# Aux_Board_V5_2.net
KiCad netlist of a schematic drawn in EAGLE
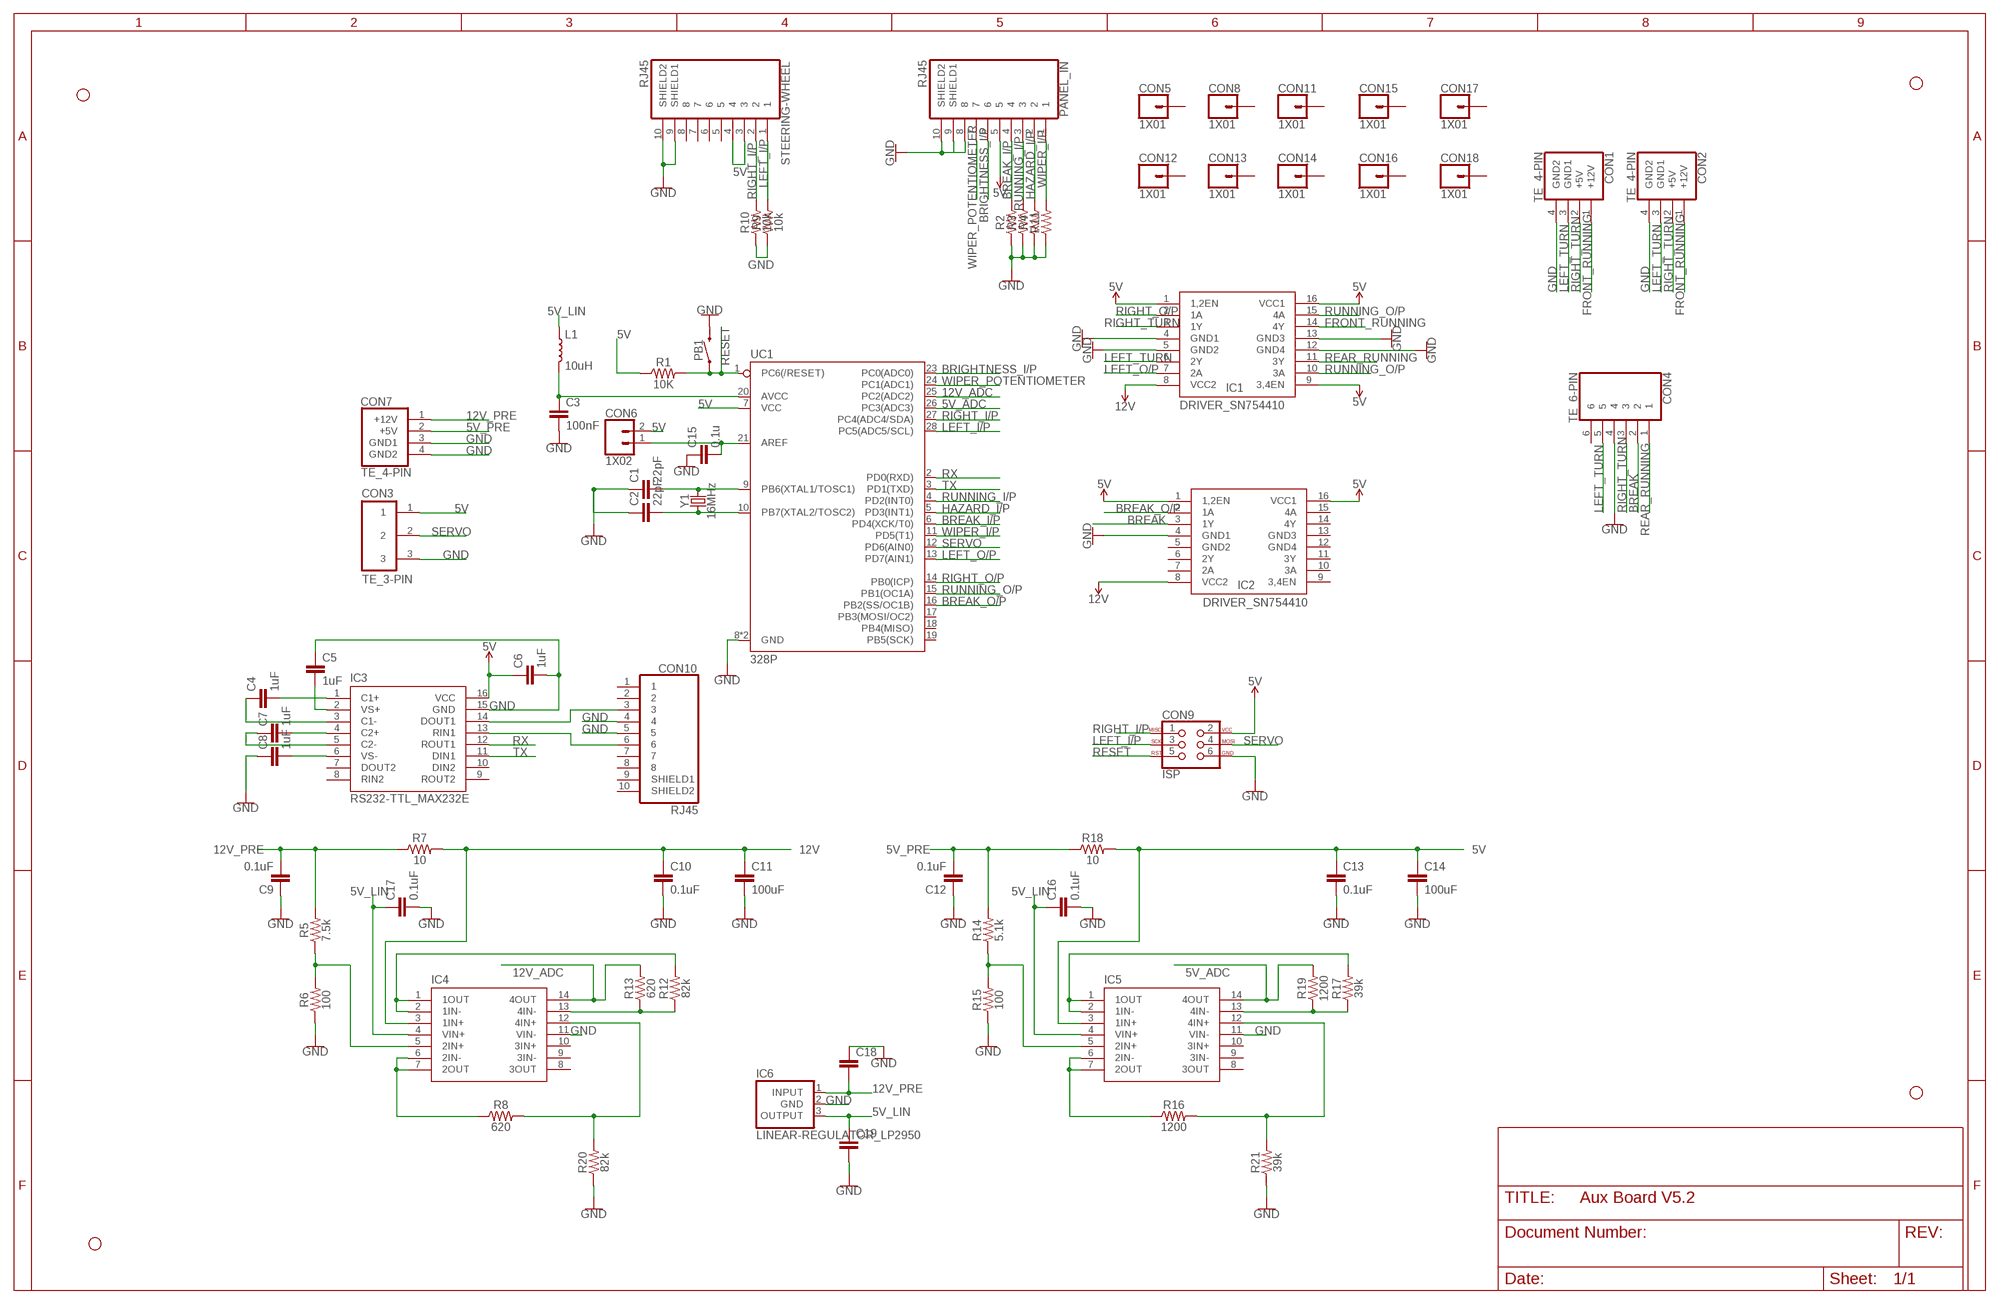
[diagram p0: schematic, sheet 1]

(export (version "E")
  (design (tool "Eeschema 10.0.6"))
  (components
    (comp (ref "C1")
      (value "22pF")
      (footprint "eagle-import:0805")
      (libsource (lib "eagle-import") (part "CAPACITOR_0805"))
    )
    (comp (ref "C2")
      (value "22pF")
      (footprint "eagle-import:0805")
      (libsource (lib "eagle-import") (part "CAPACITOR_0805"))
    )
    (comp (ref "C3")
      (value "100nF")
      (footprint "eagle-import:0805")
      (libsource (lib "eagle-import") (part "CAPACITOR_0805"))
    )
    (comp (ref "C4")
      (value "1uF")
      (footprint "eagle-import:0805")
      (libsource (lib "eagle-import") (part "CAPACITOR_0805"))
    )
    (comp (ref "C5")
      (value "1uF")
      (footprint "eagle-import:0805")
      (libsource (lib "eagle-import") (part "CAPACITOR_0805"))
    )
    (comp (ref "C6")
      (value "1uF")
      (footprint "eagle-import:0805")
      (libsource (lib "eagle-import") (part "CAPACITOR_0805"))
    )
    (comp (ref "C7")
      (value "1uF")
      (footprint "eagle-import:0805")
      (libsource (lib "eagle-import") (part "CAPACITOR_0805"))
    )
    (comp (ref "C8")
      (value "1uF")
      (footprint "eagle-import:0805")
      (libsource (lib "eagle-import") (part "CAPACITOR_0805"))
    )
    (comp (ref "C9")
      (value "0.1uF")
      (footprint "eagle-import:0805")
      (libsource (lib "eagle-import") (part "CAPACITOR_0805"))
    )
    (comp (ref "C10")
      (value "0.1uF")
      (footprint "eagle-import:0805")
      (libsource (lib "eagle-import") (part "CAPACITOR_0805"))
    )
    (comp (ref "C11")
      (value "100uF")
      (footprint "eagle-import:0805")
      (libsource (lib "eagle-import") (part "CAPACITOR_0805"))
    )
    (comp (ref "C12")
      (value "0.1uF")
      (footprint "eagle-import:0805")
      (libsource (lib "eagle-import") (part "CAPACITOR_0805"))
    )
    (comp (ref "C13")
      (value "0.1uF")
      (footprint "eagle-import:0805")
      (libsource (lib "eagle-import") (part "CAPACITOR_0805"))
    )
    (comp (ref "C14")
      (value "100uF")
      (footprint "eagle-import:0805")
      (libsource (lib "eagle-import") (part "CAPACITOR_0805"))
    )
    (comp (ref "C15")
      (value "0.1u")
      (footprint "eagle-import:0805")
      (libsource (lib "eagle-import") (part "CAPACITOR_0805"))
    )
    (comp (ref "C16")
      (value "0.1uF")
      (footprint "eagle-import:0805")
      (libsource (lib "eagle-import") (part "CAPACITOR_0805"))
    )
    (comp (ref "C17")
      (value "0.1uF")
      (footprint "eagle-import:0805")
      (libsource (lib "eagle-import") (part "CAPACITOR_0805"))
    )
    (comp (ref "C18")
      (value "CAPACITOR_0805")
      (footprint "eagle-import:0805")
      (libsource (lib "eagle-import") (part "CAPACITOR_0805"))
    )
    (comp (ref "C19")
      (value "CAPACITOR_0805")
      (footprint "eagle-import:0805")
      (libsource (lib "eagle-import") (part "CAPACITOR_0805"))
    )
    (comp (ref "CON1")
      (value "TE_4-PIN")
      (footprint "eagle-import:TE_4-PIN")
      (libsource (lib "eagle-import") (part "TE_4-PIN"))
    )
    (comp (ref "CON2")
      (value "TE_4-PIN")
      (footprint "eagle-import:TE_4-PIN")
      (libsource (lib "eagle-import") (part "TE_4-PIN"))
    )
    (comp (ref "CON3")
      (value "TE_3-PIN")
      (footprint "eagle-import:TE_3-PIN")
      (libsource (lib "eagle-import") (part "TE_3-PIN"))
    )
    (comp (ref "CON4")
      (value "TE_6-PIN")
      (footprint "eagle-import:TE_6-PIN")
      (libsource (lib "eagle-import") (part "TE_6-PIN"))
    )
    (comp (ref "CON5")
      (value "1X01")
      (footprint "eagle-import:1X01")
      (libsource (lib "eagle-import") (part "1X01"))
    )
    (comp (ref "CON6")
      (value "1X02")
      (footprint "eagle-import:1X02")
      (libsource (lib "eagle-import") (part "1X02"))
    )
    (comp (ref "CON7")
      (value "TE_4-PIN")
      (footprint "eagle-import:TE_4-PIN")
      (libsource (lib "eagle-import") (part "TE_4-PIN"))
    )
    (comp (ref "CON8")
      (value "1X01")
      (footprint "eagle-import:1X01")
      (libsource (lib "eagle-import") (part "1X01"))
    )
    (comp (ref "CON9")
      (value "ISP")
      (footprint "eagle-import:ISP_CONNECTOR")
      (libsource (lib "eagle-import") (part "ISP"))
    )
    (comp (ref "CON10")
      (value "RJ45")
      (footprint "eagle-import:RJ45")
      (libsource (lib "eagle-import") (part "RJ45"))
    )
    (comp (ref "CON11")
      (value "1X01")
      (footprint "eagle-import:1X01")
      (libsource (lib "eagle-import") (part "1X01"))
    )
    (comp (ref "CON12")
      (value "1X01")
      (footprint "eagle-import:1X01")
      (libsource (lib "eagle-import") (part "1X01"))
    )
    (comp (ref "CON13")
      (value "1X01")
      (footprint "eagle-import:1X01")
      (libsource (lib "eagle-import") (part "1X01"))
    )
    (comp (ref "CON14")
      (value "1X01")
      (footprint "eagle-import:1X01")
      (libsource (lib "eagle-import") (part "1X01"))
    )
    (comp (ref "CON15")
      (value "1X01")
      (footprint "eagle-import:1X01")
      (libsource (lib "eagle-import") (part "1X01"))
    )
    (comp (ref "CON16")
      (value "1X01")
      (footprint "eagle-import:1X01")
      (libsource (lib "eagle-import") (part "1X01"))
    )
    (comp (ref "CON17")
      (value "1X01")
      (footprint "eagle-import:1X01")
      (libsource (lib "eagle-import") (part "1X01"))
    )
    (comp (ref "CON18")
      (value "1X01")
      (footprint "eagle-import:1X01")
      (libsource (lib "eagle-import") (part "1X01"))
    )
    (comp (ref "H1")
      (value "STAND-OFF")
      (footprint "eagle-import:STAND-OFF")
      (libsource (lib "eagle-import") (part "STAND-OFF"))
    )
    (comp (ref "H2")
      (value "STAND-OFF")
      (footprint "eagle-import:STAND-OFF")
      (libsource (lib "eagle-import") (part "STAND-OFF"))
    )
    (comp (ref "H3")
      (value "STAND-OFF")
      (footprint "eagle-import:STAND-OFF")
      (libsource (lib "eagle-import") (part "STAND-OFF"))
    )
    (comp (ref "H4")
      (value "STAND-OFF")
      (footprint "eagle-import:STAND-OFF")
      (libsource (lib "eagle-import") (part "STAND-OFF"))
    )
    (comp (ref "IC1")
      (value "DRIVER_SN754410")
      (footprint "eagle-import:DIP16")
      (libsource (lib "eagle-import") (part "DRIVER_SN754410"))
    )
    (comp (ref "IC2")
      (value "DRIVER_SN754410")
      (footprint "eagle-import:DIP16")
      (libsource (lib "eagle-import") (part "DRIVER_SN754410"))
    )
    (comp (ref "IC3")
      (value "RS232-TTL_MAX232E")
      (footprint "eagle-import:DIP16")
      (libsource (lib "eagle-import") (part "RS232-TTL_MAX232E"))
    )
    (comp (ref "IC4")
      (value "OP-AMP_QUAD")
      (footprint "eagle-import:DIP14")
      (libsource (lib "eagle-import") (part "OP-AMP_QUAD"))
    )
    (comp (ref "IC5")
      (value "OP-AMP_QUAD")
      (footprint "eagle-import:DIP14")
      (libsource (lib "eagle-import") (part "OP-AMP_QUAD"))
    )
    (comp (ref "IC6")
      (value "LINEAR-REGULATOR_LP2950")
      (footprint "eagle-import:TO92")
      (libsource (lib "eagle-import") (part "LINEAR-REGULATOR_LP2950"))
    )
    (comp (ref "L1")
      (value "10uH")
      (footprint "eagle-import:0805")
      (libsource (lib "eagle-import") (part "INDUCTOR_0805"))
    )
    (comp (ref "PANEL_IN")
      (value "RJ45")
      (footprint "eagle-import:RJ45")
      (libsource (lib "eagle-import") (part "RJ45"))
    )
    (comp (ref "PB1")
      (value "PUSHBUTTON")
      (footprint "eagle-import:PUSHBUTTON")
      (libsource (lib "eagle-import") (part "PUSHBUTTON"))
    )
    (comp (ref "R1")
      (value "10K")
      (footprint "eagle-import:0805")
      (libsource (lib "eagle-import") (part "RESISTOR_0805"))
    )
    (comp (ref "R2")
      (value "RESISTOR_0805")
      (footprint "eagle-import:0805")
      (libsource (lib "eagle-import") (part "RESISTOR_0805"))
    )
    (comp (ref "R3")
      (value "RESISTOR_0805")
      (footprint "eagle-import:0805")
      (libsource (lib "eagle-import") (part "RESISTOR_0805"))
    )
    (comp (ref "R4")
      (value "RESISTOR_0805")
      (footprint "eagle-import:0805")
      (libsource (lib "eagle-import") (part "RESISTOR_0805"))
    )
    (comp (ref "R5")
      (value "7.5k")
      (footprint "eagle-import:0805")
      (libsource (lib "eagle-import") (part "RESISTOR_0805"))
    )
    (comp (ref "R6")
      (value "100")
      (footprint "eagle-import:0805")
      (libsource (lib "eagle-import") (part "RESISTOR_0805"))
    )
    (comp (ref "R7")
      (value "10")
      (footprint "eagle-import:1210")
      (libsource (lib "eagle-import") (part "RESISTOR_1210"))
    )
    (comp (ref "R8")
      (value "620")
      (footprint "eagle-import:0805")
      (libsource (lib "eagle-import") (part "RESISTOR_0805"))
    )
    (comp (ref "R9")
      (value "10k")
      (footprint "eagle-import:0805")
      (libsource (lib "eagle-import") (part "RESISTOR_0805"))
    )
    (comp (ref "R10")
      (value "10k")
      (footprint "eagle-import:0805")
      (libsource (lib "eagle-import") (part "RESISTOR_0805"))
    )
    (comp (ref "R11")
      (value "RESISTOR_0805")
      (footprint "eagle-import:0805")
      (libsource (lib "eagle-import") (part "RESISTOR_0805"))
    )
    (comp (ref "R12")
      (value "82k")
      (footprint "eagle-import:0805")
      (libsource (lib "eagle-import") (part "RESISTOR_0805"))
    )
    (comp (ref "R13")
      (value "620")
      (footprint "eagle-import:0805")
      (libsource (lib "eagle-import") (part "RESISTOR_0805"))
    )
    (comp (ref "R14")
      (value "5.1k")
      (footprint "eagle-import:0805")
      (libsource (lib "eagle-import") (part "RESISTOR_0805"))
    )
    (comp (ref "R15")
      (value "100")
      (footprint "eagle-import:0805")
      (libsource (lib "eagle-import") (part "RESISTOR_0805"))
    )
    (comp (ref "R16")
      (value "1200")
      (footprint "eagle-import:0805")
      (libsource (lib "eagle-import") (part "RESISTOR_0805"))
    )
    (comp (ref "R17")
      (value "39k")
      (footprint "eagle-import:0805")
      (libsource (lib "eagle-import") (part "RESISTOR_0805"))
    )
    (comp (ref "R18")
      (value "10")
      (footprint "eagle-import:1210")
      (libsource (lib "eagle-import") (part "RESISTOR_1210"))
    )
    (comp (ref "R19")
      (value "1200")
      (footprint "eagle-import:0805")
      (libsource (lib "eagle-import") (part "RESISTOR_0805"))
    )
    (comp (ref "R20")
      (value "82k")
      (footprint "eagle-import:0805")
      (libsource (lib "eagle-import") (part "RESISTOR_0805"))
    )
    (comp (ref "R21")
      (value "39k")
      (footprint "eagle-import:0805")
      (libsource (lib "eagle-import") (part "RESISTOR_0805"))
    )
    (comp (ref "STEERING-WHEEL")
      (value "RJ45")
      (footprint "eagle-import:RJ45")
      (libsource (lib "eagle-import") (part "RJ45"))
    )
    (comp (ref "UC1")
      (value "328P")
      (footprint "eagle-import:DIP28")
      (libsource (lib "eagle-import") (part "ATMEGA328P_DIP28"))
    )
    (comp (ref "Y1")
      (value "16MHz")
      (footprint "eagle-import:HC49US")
      (libsource (lib "eagle-import") (part "CRYSTAL-16MHZPTH-HC49US"))
    )
  )
  (nets
    (net (code "1") (name "/5V_ADC") (class "Default")
      (node (ref "IC5") (pin "14") (pinfunction "4OUT_14") (pintype "bidirectional"))
      (node (ref "R19") (pin "2") (pinfunction "2_2") (pintype "passive"))
      (node (ref "UC1") (pin "26") (pinfunction "PC3(ADC3)_26") (pintype "bidirectional"))
    )
    (net (code "2") (name "/5V_LIN") (class "Default")
      (node (ref "C16") (pin "1") (pinfunction "1_1") (pintype "passive"))
      (node (ref "C17") (pin "1") (pinfunction "1_1") (pintype "passive"))
      (node (ref "C19") (pin "1") (pinfunction "1_1") (pintype "passive"))
      (node (ref "IC4") (pin "4") (pinfunction "VIN+_4") (pintype "bidirectional"))
      (node (ref "IC5") (pin "4") (pinfunction "VIN+_4") (pintype "bidirectional"))
      (node (ref "IC6") (pin "3") (pinfunction "OUTPUT_3") (pintype "bidirectional"))
      (node (ref "L1") (pin "1") (pinfunction "1_1") (pintype "passive"))
    )
    (net (code "3") (name "/5V_PRE") (class "Default")
      (node (ref "C12") (pin "2") (pinfunction "2_2") (pintype "passive"))
      (node (ref "CON7") (pin "2") (pinfunction "+5V_2") (pintype "passive"))
      (node (ref "R14") (pin "2") (pinfunction "2_2") (pintype "passive"))
      (node (ref "R18") (pin "1") (pinfunction "1_1") (pintype "passive"))
    )
    (net (code "4") (name "/12V_ADC") (class "Default")
      (node (ref "IC4") (pin "14") (pinfunction "4OUT_14") (pintype "bidirectional"))
      (node (ref "R13") (pin "2") (pinfunction "2_2") (pintype "passive"))
      (node (ref "UC1") (pin "25") (pinfunction "PC2(ADC2)_25") (pintype "bidirectional"))
    )
    (net (code "5") (name "/12V_PRE") (class "Default")
      (node (ref "C18") (pin "2") (pinfunction "2_2") (pintype "passive"))
      (node (ref "C9") (pin "2") (pinfunction "2_2") (pintype "passive"))
      (node (ref "CON7") (pin "1") (pinfunction "+12V_1") (pintype "passive"))
      (node (ref "IC6") (pin "1") (pinfunction "INPUT_1") (pintype "bidirectional"))
      (node (ref "R5") (pin "2") (pinfunction "2_2") (pintype "passive"))
      (node (ref "R7") (pin "1") (pinfunction "1_1") (pintype "passive"))
    )
    (net (code "6") (name "/BREAK") (class "Default")
      (node (ref "CON4") (pin "2") (pinfunction "2_2") (pintype "passive"))
      (node (ref "IC2") (pin "3") (pinfunction "1Y_3") (pintype "bidirectional"))
    )
    (net (code "7") (name "/BREAK_I{slash}P") (class "Default")
      (node (ref "PANEL_IN") (pin "4") (pinfunction "4_4") (pintype "passive"))
      (node (ref "R2") (pin "2") (pinfunction "2_2") (pintype "passive"))
      (node (ref "UC1") (pin "6") (pinfunction "PD4(XCK/T0)_6") (pintype "bidirectional"))
    )
    (net (code "8") (name "/BREAK_O{slash}P") (class "Default")
      (node (ref "IC2") (pin "2") (pinfunction "1A_2") (pintype "bidirectional"))
      (node (ref "UC1") (pin "16") (pinfunction "PB2(SS/OC1B)_16") (pintype "bidirectional"))
    )
    (net (code "9") (name "/BRIGHTNESS_I{slash}P") (class "Default")
      (node (ref "PANEL_IN") (pin "6") (pinfunction "6_6") (pintype "passive"))
      (node (ref "UC1") (pin "23") (pinfunction "PC0(ADC0)_23") (pintype "bidirectional"))
    )
    (net (code "10") (name "/FRONT_RUNNING") (class "Default")
      (node (ref "CON1") (pin "1") (pinfunction "+12V_1") (pintype "passive"))
      (node (ref "CON2") (pin "1") (pinfunction "+12V_1") (pintype "passive"))
      (node (ref "IC1") (pin "14") (pinfunction "4Y_14") (pintype "bidirectional"))
    )
    (net (code "11") (name "/HAZARD_I{slash}P") (class "Default")
      (node (ref "PANEL_IN") (pin "2") (pinfunction "2_2") (pintype "passive"))
      (node (ref "R4") (pin "2") (pinfunction "2_2") (pintype "passive"))
      (node (ref "UC1") (pin "5") (pinfunction "PD3(INT1)_5") (pintype "bidirectional"))
    )
    (net (code "12") (name "/LEFT_I{slash}P") (class "Default")
      (node (ref "CON9") (pin "3") (pinfunction "3_3") (pintype "passive"))
      (node (ref "R9") (pin "2") (pinfunction "2_2") (pintype "passive"))
      (node (ref "STEERING-WHEEL") (pin "1") (pinfunction "1_1") (pintype "passive"))
      (node (ref "UC1") (pin "28") (pinfunction "PC5(ADC5/SCL)_28") (pintype "bidirectional"))
    )
    (net (code "13") (name "/LEFT_O{slash}P") (class "Default")
      (node (ref "IC1") (pin "7") (pinfunction "2A_7") (pintype "bidirectional"))
      (node (ref "UC1") (pin "13") (pinfunction "PD7(AIN1)_13") (pintype "bidirectional"))
    )
    (net (code "14") (name "/LEFT_TURN") (class "Default")
      (node (ref "CON1") (pin "3") (pinfunction "GND1_3") (pintype "passive"))
      (node (ref "CON2") (pin "3") (pinfunction "GND1_3") (pintype "passive"))
      (node (ref "CON4") (pin "5") (pinfunction "5_5") (pintype "passive"))
      (node (ref "IC1") (pin "6") (pinfunction "2Y_6") (pintype "bidirectional"))
    )
    (net (code "15") (name "/REAR_RUNNING") (class "Default")
      (node (ref "CON4") (pin "1") (pinfunction "1_1") (pintype "passive"))
      (node (ref "IC1") (pin "11") (pinfunction "3Y_11") (pintype "bidirectional"))
    )
    (net (code "16") (name "/RESET") (class "Default")
      (node (ref "CON9") (pin "5") (pinfunction "5_5") (pintype "passive"))
      (node (ref "PB1") (pin "1") (pinfunction "1_1") (pintype "passive"))
      (node (ref "PB1") (pin "2") (pinfunction "1_2") (pintype "passive"))
      (node (ref "R1") (pin "2") (pinfunction "2_2") (pintype "passive"))
      (node (ref "UC1") (pin "1") (pinfunction "PC6(/RESET)_1") (pintype "bidirectional"))
    )
    (net (code "17") (name "/RIGHT_I{slash}P") (class "Default")
      (node (ref "CON9") (pin "1") (pinfunction "1_1") (pintype "passive"))
      (node (ref "R10") (pin "2") (pinfunction "2_2") (pintype "passive"))
      (node (ref "STEERING-WHEEL") (pin "2") (pinfunction "2_2") (pintype "passive"))
      (node (ref "UC1") (pin "27") (pinfunction "PC4(ADC4/SDA)_27") (pintype "bidirectional"))
    )
    (net (code "18") (name "/RIGHT_O{slash}P") (class "Default")
      (node (ref "IC1") (pin "2") (pinfunction "1A_2") (pintype "bidirectional"))
      (node (ref "UC1") (pin "14") (pinfunction "PB0(ICP)_14") (pintype "bidirectional"))
    )
    (net (code "19") (name "/RIGHT_TURN") (class "Default")
      (node (ref "CON1") (pin "2") (pinfunction "+5V_2") (pintype "passive"))
      (node (ref "CON2") (pin "2") (pinfunction "+5V_2") (pintype "passive"))
      (node (ref "CON4") (pin "3") (pinfunction "3_3") (pintype "passive"))
      (node (ref "IC1") (pin "3") (pinfunction "1Y_3") (pintype "bidirectional"))
    )
    (net (code "20") (name "/RUNNING_I{slash}P") (class "Default")
      (node (ref "PANEL_IN") (pin "3") (pinfunction "3_3") (pintype "passive"))
      (node (ref "R3") (pin "2") (pinfunction "2_2") (pintype "passive"))
      (node (ref "UC1") (pin "4") (pinfunction "PD2(INT0)_4") (pintype "bidirectional"))
    )
    (net (code "21") (name "/RUNNING_O{slash}P") (class "Default")
      (node (ref "IC1") (pin "10") (pinfunction "3A_10") (pintype "bidirectional"))
      (node (ref "IC1") (pin "15") (pinfunction "4A_15") (pintype "bidirectional"))
      (node (ref "UC1") (pin "15") (pinfunction "PB1(OC1A)_15") (pintype "bidirectional"))
    )
    (net (code "22") (name "/RX") (class "Default")
      (node (ref "IC3") (pin "12") (pinfunction "ROUT1_12") (pintype "bidirectional"))
      (node (ref "UC1") (pin "2") (pinfunction "PD0(RXD)_2") (pintype "bidirectional"))
    )
    (net (code "23") (name "/SERVO") (class "Default")
      (node (ref "CON3") (pin "2") (pinfunction "2_2") (pintype "passive"))
      (node (ref "CON9") (pin "4") (pinfunction "4_4") (pintype "passive"))
      (node (ref "UC1") (pin "12") (pinfunction "PD6(AIN0)_12") (pintype "bidirectional"))
    )
    (net (code "24") (name "/TX") (class "Default")
      (node (ref "IC3") (pin "11") (pinfunction "DIN1_11") (pintype "bidirectional"))
      (node (ref "UC1") (pin "3") (pinfunction "PD1(TXD)_3") (pintype "bidirectional"))
    )
    (net (code "25") (name "/WIPER_I{slash}P") (class "Default")
      (node (ref "PANEL_IN") (pin "1") (pinfunction "1_1") (pintype "passive"))
      (node (ref "R11") (pin "2") (pinfunction "2_2") (pintype "passive"))
      (node (ref "UC1") (pin "11") (pinfunction "PD5(T1)_11") (pintype "bidirectional"))
    )
    (net (code "26") (name "/WIPER_POTENTIOMETER") (class "Default")
      (node (ref "PANEL_IN") (pin "7") (pinfunction "7_7") (pintype "passive"))
      (node (ref "UC1") (pin "24") (pinfunction "PC1(ADC1)_24") (pintype "bidirectional"))
    )
    (net (code "27") (name "5V") (class "Default")
      (node (ref "C13") (pin "1") (pinfunction "1_1") (pintype "passive"))
      (node (ref "C14") (pin "1") (pinfunction "1_1") (pintype "passive"))
      (node (ref "C15") (pin "2") (pinfunction "2_2") (pintype "passive"))
      (node (ref "C6") (pin "1") (pinfunction "1_1") (pintype "passive"))
      (node (ref "CON3") (pin "1") (pinfunction "1_1") (pintype "passive"))
      (node (ref "CON6") (pin "1") (pinfunction "1_1") (pintype "passive"))
      (node (ref "CON6") (pin "2") (pinfunction "2_2") (pintype "passive"))
      (node (ref "CON9") (pin "2") (pinfunction "2_2") (pintype "passive"))
      (node (ref "IC1") (pin "1") (pinfunction "1,2EN_1") (pintype "bidirectional"))
      (node (ref "IC1") (pin "16") (pinfunction "VCC1_16") (pintype "bidirectional"))
      (node (ref "IC1") (pin "9") (pinfunction "3,4EN_9") (pintype "bidirectional"))
      (node (ref "IC2") (pin "1") (pinfunction "1,2EN_1") (pintype "bidirectional"))
      (node (ref "IC2") (pin "16") (pinfunction "VCC1_16") (pintype "bidirectional"))
      (node (ref "IC3") (pin "16") (pinfunction "VCC_16") (pintype "bidirectional"))
      (node (ref "IC5") (pin "3") (pinfunction "1IN+_3") (pintype "bidirectional"))
      (node (ref "PANEL_IN") (pin "5") (pinfunction "5_5") (pintype "passive"))
      (node (ref "R1") (pin "1") (pinfunction "1_1") (pintype "passive"))
      (node (ref "R18") (pin "2") (pinfunction "2_2") (pintype "passive"))
      (node (ref "STEERING-WHEEL") (pin "3") (pinfunction "3_3") (pintype "passive"))
      (node (ref "STEERING-WHEEL") (pin "4") (pinfunction "4_4") (pintype "passive"))
      (node (ref "UC1") (pin "21") (pinfunction "AREF_21") (pintype "bidirectional"))
      (node (ref "UC1") (pin "7") (pinfunction "VCC_7") (pintype "bidirectional"))
    )
    (net (code "28") (name "12V") (class "Default")
      (node (ref "C10") (pin "1") (pinfunction "1_1") (pintype "passive"))
      (node (ref "C11") (pin "1") (pinfunction "1_1") (pintype "passive"))
      (node (ref "IC1") (pin "8") (pinfunction "VCC2_8") (pintype "bidirectional"))
      (node (ref "IC2") (pin "8") (pinfunction "VCC2_8") (pintype "bidirectional"))
      (node (ref "IC4") (pin "3") (pinfunction "1IN+_3") (pintype "bidirectional"))
      (node (ref "R7") (pin "2") (pinfunction "2_2") (pintype "passive"))
    )
    (net (code "29") (name "GND") (class "Default")
      (node (ref "C1") (pin "1") (pinfunction "1_1") (pintype "passive"))
      (node (ref "C10") (pin "2") (pinfunction "2_2") (pintype "passive"))
      (node (ref "C11") (pin "2") (pinfunction "2_2") (pintype "passive"))
      (node (ref "C12") (pin "1") (pinfunction "1_1") (pintype "passive"))
      (node (ref "C13") (pin "2") (pinfunction "2_2") (pintype "passive"))
      (node (ref "C14") (pin "2") (pinfunction "2_2") (pintype "passive"))
      (node (ref "C15") (pin "1") (pinfunction "1_1") (pintype "passive"))
      (node (ref "C16") (pin "2") (pinfunction "2_2") (pintype "passive"))
      (node (ref "C17") (pin "2") (pinfunction "2_2") (pintype "passive"))
      (node (ref "C18") (pin "1") (pinfunction "1_1") (pintype "passive"))
      (node (ref "C19") (pin "2") (pinfunction "2_2") (pintype "passive"))
      (node (ref "C2") (pin "1") (pinfunction "1_1") (pintype "passive"))
      (node (ref "C3") (pin "2") (pinfunction "2_2") (pintype "passive"))
      (node (ref "C5") (pin "1") (pinfunction "1_1") (pintype "passive"))
      (node (ref "C6") (pin "2") (pinfunction "2_2") (pintype "passive"))
      (node (ref "C8") (pin "1") (pinfunction "1_1") (pintype "passive"))
      (node (ref "C9") (pin "1") (pinfunction "1_1") (pintype "passive"))
      (node (ref "CON1") (pin "4") (pinfunction "GND2_4") (pintype "passive"))
      (node (ref "CON10") (pin "4") (pinfunction "4_4") (pintype "passive"))
      (node (ref "CON10") (pin "5") (pinfunction "5_5") (pintype "passive"))
      (node (ref "CON2") (pin "4") (pinfunction "GND2_4") (pintype "passive"))
      (node (ref "CON3") (pin "3") (pinfunction "3_3") (pintype "passive"))
      (node (ref "CON4") (pin "4") (pinfunction "4_4") (pintype "passive"))
      (node (ref "CON7") (pin "3") (pinfunction "GND1_3") (pintype "passive"))
      (node (ref "CON7") (pin "4") (pinfunction "GND2_4") (pintype "passive"))
      (node (ref "CON9") (pin "6") (pinfunction "6_6") (pintype "passive"))
      (node (ref "IC1") (pin "12") (pinfunction "GND4_12") (pintype "bidirectional"))
      (node (ref "IC1") (pin "13") (pinfunction "GND3_13") (pintype "bidirectional"))
      (node (ref "IC1") (pin "4") (pinfunction "GND1_4") (pintype "bidirectional"))
      (node (ref "IC1") (pin "5") (pinfunction "GND2_5") (pintype "bidirectional"))
      (node (ref "IC2") (pin "4") (pinfunction "GND1_4") (pintype "bidirectional"))
      (node (ref "IC3") (pin "15") (pinfunction "GND_15") (pintype "bidirectional"))
      (node (ref "IC4") (pin "11") (pinfunction "VIN-_11") (pintype "bidirectional"))
      (node (ref "IC5") (pin "11") (pinfunction "VIN-_11") (pintype "bidirectional"))
      (node (ref "IC6") (pin "2") (pinfunction "GND_2") (pintype "bidirectional"))
      (node (ref "PANEL_IN") (pin "10") (pinfunction "SHIELD2_10") (pintype "passive"))
      (node (ref "PANEL_IN") (pin "8") (pinfunction "8_8") (pintype "passive"))
      (node (ref "PANEL_IN") (pin "9") (pinfunction "SHIELD1_9") (pintype "passive"))
      (node (ref "PB1") (pin "3") (pinfunction "2_3") (pintype "passive"))
      (node (ref "PB1") (pin "4") (pinfunction "2_4") (pintype "passive"))
      (node (ref "R10") (pin "1") (pinfunction "1_1") (pintype "passive"))
      (node (ref "R11") (pin "1") (pinfunction "1_1") (pintype "passive"))
      (node (ref "R15") (pin "1") (pinfunction "1_1") (pintype "passive"))
      (node (ref "R2") (pin "1") (pinfunction "1_1") (pintype "passive"))
      (node (ref "R20") (pin "1") (pinfunction "1_1") (pintype "passive"))
      (node (ref "R21") (pin "1") (pinfunction "1_1") (pintype "passive"))
      (node (ref "R3") (pin "1") (pinfunction "1_1") (pintype "passive"))
      (node (ref "R4") (pin "1") (pinfunction "1_1") (pintype "passive"))
      (node (ref "R6") (pin "1") (pinfunction "1_1") (pintype "passive"))
      (node (ref "R9") (pin "1") (pinfunction "1_1") (pintype "passive"))
      (node (ref "STEERING-WHEEL") (pin "10") (pinfunction "SHIELD2_10") (pintype "passive"))
      (node (ref "STEERING-WHEEL") (pin "9") (pinfunction "SHIELD1_9") (pintype "passive"))
      (node (ref "UC1") (pin "22") (pinfunction "GND_22") (pintype "bidirectional"))
      (node (ref "UC1") (pin "8") (pinfunction "GND_8") (pintype "bidirectional"))
    )
    (net (code "30") (name "Net-(IC3-C1+)") (class "Default")
      (node (ref "C4") (pin "2") (pinfunction "2_2") (pintype "passive"))
      (node (ref "IC3") (pin "1") (pinfunction "C1+_1") (pintype "bidirectional"))
    )
    (net (code "31") (name "Net-(IC3-C1-)") (class "Default")
      (node (ref "C4") (pin "1") (pinfunction "1_1") (pintype "passive"))
      (node (ref "IC3") (pin "3") (pinfunction "C1-_3") (pintype "bidirectional"))
    )
    (net (code "32") (name "Net-(IC3-C2+)") (class "Default")
      (node (ref "C7") (pin "2") (pinfunction "2_2") (pintype "passive"))
      (node (ref "IC3") (pin "4") (pinfunction "C2+_4") (pintype "bidirectional"))
    )
    (net (code "33") (name "Net-(IC3-C2-)") (class "Default")
      (node (ref "C7") (pin "1") (pinfunction "1_1") (pintype "passive"))
      (node (ref "IC3") (pin "5") (pinfunction "C2-_5") (pintype "bidirectional"))
    )
    (net (code "34") (name "Net-(IC3-DOUT1)") (class "Default")
      (node (ref "CON10") (pin "3") (pinfunction "3_3") (pintype "passive"))
      (node (ref "IC3") (pin "14") (pinfunction "DOUT1_14") (pintype "bidirectional"))
    )
    (net (code "35") (name "Net-(IC3-RIN1)") (class "Default")
      (node (ref "CON10") (pin "6") (pinfunction "6_6") (pintype "passive"))
      (node (ref "IC3") (pin "13") (pinfunction "RIN1_13") (pintype "bidirectional"))
    )
    (net (code "36") (name "Net-(IC3-VS+)") (class "Default")
      (node (ref "C5") (pin "2") (pinfunction "2_2") (pintype "passive"))
      (node (ref "IC3") (pin "2") (pinfunction "VS+_2") (pintype "bidirectional"))
    )
    (net (code "37") (name "Net-(IC3-VS-)") (class "Default")
      (node (ref "C8") (pin "2") (pinfunction "2_2") (pintype "passive"))
      (node (ref "IC3") (pin "6") (pinfunction "VS-_6") (pintype "bidirectional"))
    )
    (net (code "38") (name "Net-(IC4-1IN-)") (class "Default")
      (node (ref "IC4") (pin "1") (pinfunction "1OUT_1") (pintype "bidirectional"))
      (node (ref "IC4") (pin "2") (pinfunction "1IN-_2") (pintype "bidirectional"))
      (node (ref "R12") (pin "2") (pinfunction "2_2") (pintype "passive"))
    )
    (net (code "39") (name "Net-(IC4-2IN+)") (class "Default")
      (node (ref "IC4") (pin "5") (pinfunction "2IN+_5") (pintype "bidirectional"))
      (node (ref "R5") (pin "1") (pinfunction "1_1") (pintype "passive"))
      (node (ref "R6") (pin "2") (pinfunction "2_2") (pintype "passive"))
    )
    (net (code "40") (name "Net-(IC4-2IN-)") (class "Default")
      (node (ref "IC4") (pin "6") (pinfunction "2IN-_6") (pintype "bidirectional"))
      (node (ref "IC4") (pin "7") (pinfunction "2OUT_7") (pintype "bidirectional"))
      (node (ref "R8") (pin "1") (pinfunction "1_1") (pintype "passive"))
    )
    (net (code "41") (name "Net-(IC4-4IN+)") (class "Default")
      (node (ref "IC4") (pin "12") (pinfunction "4IN+_12") (pintype "bidirectional"))
      (node (ref "R20") (pin "2") (pinfunction "2_2") (pintype "passive"))
      (node (ref "R8") (pin "2") (pinfunction "2_2") (pintype "passive"))
    )
    (net (code "42") (name "Net-(IC4-4IN-)") (class "Default")
      (node (ref "IC4") (pin "13") (pinfunction "4IN-_13") (pintype "bidirectional"))
      (node (ref "R12") (pin "1") (pinfunction "1_1") (pintype "passive"))
      (node (ref "R13") (pin "1") (pinfunction "1_1") (pintype "passive"))
    )
    (net (code "43") (name "Net-(IC5-1IN-)") (class "Default")
      (node (ref "IC5") (pin "1") (pinfunction "1OUT_1") (pintype "bidirectional"))
      (node (ref "IC5") (pin "2") (pinfunction "1IN-_2") (pintype "bidirectional"))
      (node (ref "R17") (pin "2") (pinfunction "2_2") (pintype "passive"))
    )
    (net (code "44") (name "Net-(IC5-2IN+)") (class "Default")
      (node (ref "IC5") (pin "5") (pinfunction "2IN+_5") (pintype "bidirectional"))
      (node (ref "R14") (pin "1") (pinfunction "1_1") (pintype "passive"))
      (node (ref "R15") (pin "2") (pinfunction "2_2") (pintype "passive"))
    )
    (net (code "45") (name "Net-(IC5-2IN-)") (class "Default")
      (node (ref "IC5") (pin "6") (pinfunction "2IN-_6") (pintype "bidirectional"))
      (node (ref "IC5") (pin "7") (pinfunction "2OUT_7") (pintype "bidirectional"))
      (node (ref "R16") (pin "1") (pinfunction "1_1") (pintype "passive"))
    )
    (net (code "46") (name "Net-(IC5-4IN+)") (class "Default")
      (node (ref "IC5") (pin "12") (pinfunction "4IN+_12") (pintype "bidirectional"))
      (node (ref "R16") (pin "2") (pinfunction "2_2") (pintype "passive"))
      (node (ref "R21") (pin "2") (pinfunction "2_2") (pintype "passive"))
    )
    (net (code "47") (name "Net-(IC5-4IN-)") (class "Default")
      (node (ref "IC5") (pin "13") (pinfunction "4IN-_13") (pintype "bidirectional"))
      (node (ref "R17") (pin "1") (pinfunction "1_1") (pintype "passive"))
      (node (ref "R19") (pin "1") (pinfunction "1_1") (pintype "passive"))
    )
    (net (code "48") (name "Net-(UC1-AVCC)") (class "Default")
      (node (ref "C3") (pin "1") (pinfunction "1_1") (pintype "passive"))
      (node (ref "L1") (pin "2") (pinfunction "2_2") (pintype "passive"))
      (node (ref "UC1") (pin "20") (pinfunction "AVCC_20") (pintype "bidirectional"))
    )
    (net (code "49") (name "Net-(UC1-PB6(XTAL1{slash}TOSC1))") (class "Default")
      (node (ref "C1") (pin "2") (pinfunction "2_2") (pintype "passive"))
      (node (ref "UC1") (pin "9") (pinfunction "PB6(XTAL1/TOSC1)_9") (pintype "bidirectional"))
      (node (ref "Y1") (pin "2") (pinfunction "2_2") (pintype "passive"))
    )
    (net (code "50") (name "Net-(UC1-PB7(XTAL2{slash}TOSC2))") (class "Default")
      (node (ref "C2") (pin "2") (pinfunction "2_2") (pintype "passive"))
      (node (ref "UC1") (pin "10") (pinfunction "PB7(XTAL2/TOSC2)_10") (pintype "bidirectional"))
      (node (ref "Y1") (pin "1") (pinfunction "1_1") (pintype "passive"))
    )
    (net (code "51") (name "unconnected-(CON4-Pad6)") (class "Default")
      (node (ref "CON4") (pin "6") (pinfunction "6_6") (pintype "passive"))
    )
    (net (code "52") (name "unconnected-(CON5-Pad1)") (class "Default")
      (node (ref "CON5") (pin "1") (pinfunction "1_1") (pintype "passive"))
    )
    (net (code "53") (name "unconnected-(CON8-Pad1)") (class "Default")
      (node (ref "CON8") (pin "1") (pinfunction "1_1") (pintype "passive"))
    )
    (net (code "54") (name "unconnected-(CON10-Pad1)") (class "Default")
      (node (ref "CON10") (pin "1") (pinfunction "1_1") (pintype "passive"))
    )
    (net (code "55") (name "unconnected-(CON10-Pad2)") (class "Default")
      (node (ref "CON10") (pin "2") (pinfunction "2_2") (pintype "passive"))
    )
    (net (code "56") (name "unconnected-(CON10-Pad7)") (class "Default")
      (node (ref "CON10") (pin "7") (pinfunction "7_7") (pintype "passive"))
    )
    (net (code "57") (name "unconnected-(CON10-Pad8)") (class "Default")
      (node (ref "CON10") (pin "8") (pinfunction "8_8") (pintype "passive"))
    )
    (net (code "58") (name "unconnected-(CON10-SHIELD1-Pad9)") (class "Default")
      (node (ref "CON10") (pin "9") (pinfunction "SHIELD1_9") (pintype "passive"))
    )
    (net (code "59") (name "unconnected-(CON10-SHIELD2-Pad10)") (class "Default")
      (node (ref "CON10") (pin "10") (pinfunction "SHIELD2_10") (pintype "passive"))
    )
    (net (code "60") (name "unconnected-(CON11-Pad1)") (class "Default")
      (node (ref "CON11") (pin "1") (pinfunction "1_1") (pintype "passive"))
    )
    (net (code "61") (name "unconnected-(CON12-Pad1)") (class "Default")
      (node (ref "CON12") (pin "1") (pinfunction "1_1") (pintype "passive"))
    )
    (net (code "62") (name "unconnected-(CON13-Pad1)") (class "Default")
      (node (ref "CON13") (pin "1") (pinfunction "1_1") (pintype "passive"))
    )
    (net (code "63") (name "unconnected-(CON14-Pad1)") (class "Default")
      (node (ref "CON14") (pin "1") (pinfunction "1_1") (pintype "passive"))
    )
    (net (code "64") (name "unconnected-(CON15-Pad1)") (class "Default")
      (node (ref "CON15") (pin "1") (pinfunction "1_1") (pintype "passive"))
    )
    (net (code "65") (name "unconnected-(CON16-Pad1)") (class "Default")
      (node (ref "CON16") (pin "1") (pinfunction "1_1") (pintype "passive"))
    )
    (net (code "66") (name "unconnected-(CON17-Pad1)") (class "Default")
      (node (ref "CON17") (pin "1") (pinfunction "1_1") (pintype "passive"))
    )
    (net (code "67") (name "unconnected-(CON18-Pad1)") (class "Default")
      (node (ref "CON18") (pin "1") (pinfunction "1_1") (pintype "passive"))
    )
    (net (code "68") (name "unconnected-(IC2-2A-Pad7)") (class "Default")
      (node (ref "IC2") (pin "7") (pinfunction "2A_7") (pintype "bidirectional"))
    )
    (net (code "69") (name "unconnected-(IC2-2Y-Pad6)") (class "Default")
      (node (ref "IC2") (pin "6") (pinfunction "2Y_6") (pintype "bidirectional"))
    )
    (net (code "70") (name "unconnected-(IC2-3,4EN-Pad9)") (class "Default")
      (node (ref "IC2") (pin "9") (pinfunction "3,4EN_9") (pintype "bidirectional"))
    )
    (net (code "71") (name "unconnected-(IC2-3A-Pad10)") (class "Default")
      (node (ref "IC2") (pin "10") (pinfunction "3A_10") (pintype "bidirectional"))
    )
    (net (code "72") (name "unconnected-(IC2-3Y-Pad11)") (class "Default")
      (node (ref "IC2") (pin "11") (pinfunction "3Y_11") (pintype "bidirectional"))
    )
    (net (code "73") (name "unconnected-(IC2-4A-Pad15)") (class "Default")
      (node (ref "IC2") (pin "15") (pinfunction "4A_15") (pintype "bidirectional"))
    )
    (net (code "74") (name "unconnected-(IC2-4Y-Pad14)") (class "Default")
      (node (ref "IC2") (pin "14") (pinfunction "4Y_14") (pintype "bidirectional"))
    )
    (net (code "75") (name "unconnected-(IC2-GND2-Pad5)") (class "Default")
      (node (ref "IC2") (pin "5") (pinfunction "GND2_5") (pintype "bidirectional"))
    )
    (net (code "76") (name "unconnected-(IC2-GND3-Pad13)") (class "Default")
      (node (ref "IC2") (pin "13") (pinfunction "GND3_13") (pintype "bidirectional"))
    )
    (net (code "77") (name "unconnected-(IC2-GND4-Pad12)") (class "Default")
      (node (ref "IC2") (pin "12") (pinfunction "GND4_12") (pintype "bidirectional"))
    )
    (net (code "78") (name "unconnected-(IC3-DIN2-Pad10)") (class "Default")
      (node (ref "IC3") (pin "10") (pinfunction "DIN2_10") (pintype "bidirectional"))
    )
    (net (code "79") (name "unconnected-(IC3-DOUT2-Pad7)") (class "Default")
      (node (ref "IC3") (pin "7") (pinfunction "DOUT2_7") (pintype "bidirectional"))
    )
    (net (code "80") (name "unconnected-(IC3-RIN2-Pad8)") (class "Default")
      (node (ref "IC3") (pin "8") (pinfunction "RIN2_8") (pintype "bidirectional"))
    )
    (net (code "81") (name "unconnected-(IC3-ROUT2-Pad9)") (class "Default")
      (node (ref "IC3") (pin "9") (pinfunction "ROUT2_9") (pintype "bidirectional"))
    )
    (net (code "82") (name "unconnected-(IC4-3IN+-Pad10)") (class "Default")
      (node (ref "IC4") (pin "10") (pinfunction "3IN+_10") (pintype "bidirectional"))
    )
    (net (code "83") (name "unconnected-(IC4-3IN--Pad9)") (class "Default")
      (node (ref "IC4") (pin "9") (pinfunction "3IN-_9") (pintype "bidirectional"))
    )
    (net (code "84") (name "unconnected-(IC4-3OUT-Pad8)") (class "Default")
      (node (ref "IC4") (pin "8") (pinfunction "3OUT_8") (pintype "bidirectional"))
    )
    (net (code "85") (name "unconnected-(IC5-3IN+-Pad10)") (class "Default")
      (node (ref "IC5") (pin "10") (pinfunction "3IN+_10") (pintype "bidirectional"))
    )
    (net (code "86") (name "unconnected-(IC5-3IN--Pad9)") (class "Default")
      (node (ref "IC5") (pin "9") (pinfunction "3IN-_9") (pintype "bidirectional"))
    )
    (net (code "87") (name "unconnected-(IC5-3OUT-Pad8)") (class "Default")
      (node (ref "IC5") (pin "8") (pinfunction "3OUT_8") (pintype "bidirectional"))
    )
    (net (code "88") (name "unconnected-(STEERING-WHEEL-Pad5)") (class "Default")
      (node (ref "STEERING-WHEEL") (pin "5") (pinfunction "5_5") (pintype "passive"))
    )
    (net (code "89") (name "unconnected-(STEERING-WHEEL-Pad6)") (class "Default")
      (node (ref "STEERING-WHEEL") (pin "6") (pinfunction "6_6") (pintype "passive"))
    )
    (net (code "90") (name "unconnected-(STEERING-WHEEL-Pad7)") (class "Default")
      (node (ref "STEERING-WHEEL") (pin "7") (pinfunction "7_7") (pintype "passive"))
    )
    (net (code "91") (name "unconnected-(STEERING-WHEEL-Pad8)") (class "Default")
      (node (ref "STEERING-WHEEL") (pin "8") (pinfunction "8_8") (pintype "passive"))
    )
    (net (code "92") (name "unconnected-(UC1-PB3(MOSI{slash}OC2)-Pad17)") (class "Default")
      (node (ref "UC1") (pin "17") (pinfunction "PB3(MOSI/OC2)_17") (pintype "bidirectional"))
    )
    (net (code "93") (name "unconnected-(UC1-PB4(MISO)-Pad18)") (class "Default")
      (node (ref "UC1") (pin "18") (pinfunction "PB4(MISO)_18") (pintype "bidirectional"))
    )
    (net (code "94") (name "unconnected-(UC1-PB5(SCK)-Pad19)") (class "Default")
      (node (ref "UC1") (pin "19") (pinfunction "PB5(SCK)_19") (pintype "bidirectional"))
    )
  )
)
